# CLK_MUX.net
KiCad netlist of a schematic drawn in Altium Designer
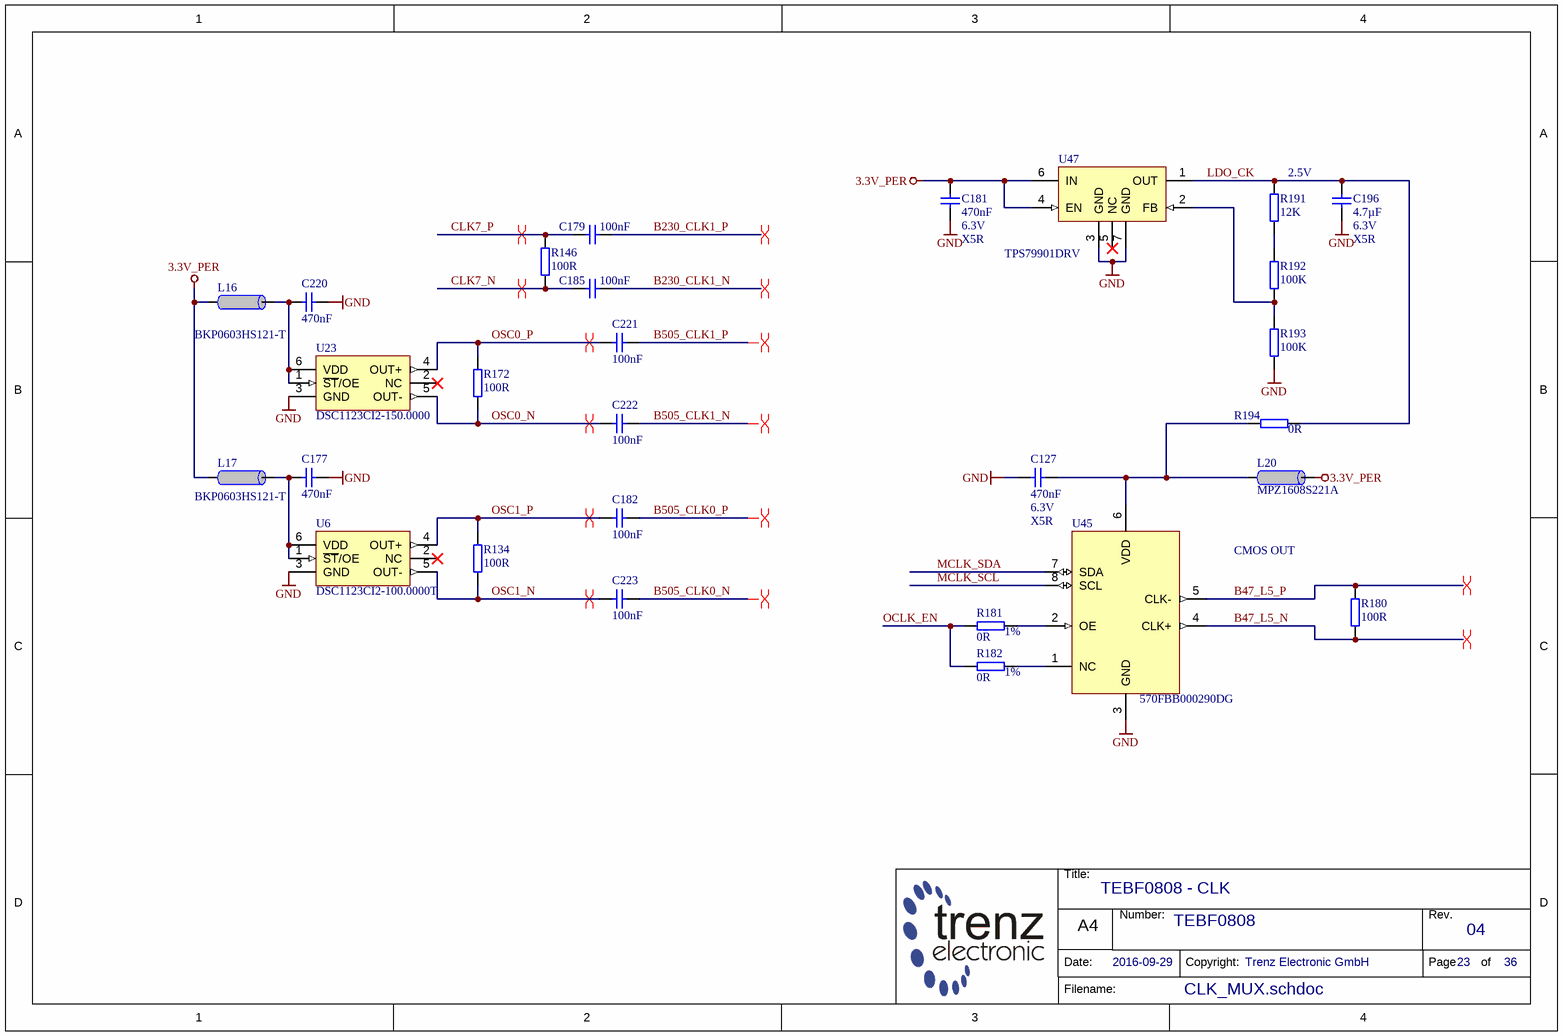
[diagram p0: CLK_MUX.schdoc]

(export (version "E")
  (design (tool "Eeschema 10.0.6"))
  (components
    (comp (ref "C127")
      (value "470nF")
      (footprint "CAPC1005X55N")
      (description "KON 470nF 6,3V X5R SMD")
      (fields (field (name "VOLTAGE") "6.3V") (field (name "TECHNOLOGY") "X5R"))
      (libsource (lib "TE") (part "CAP-NP"))
    )
    (comp (ref "C177")
      (value "470nF")
      (footprint "CAPC0603X33N")
      (description "KON 470nF X5R 6.3V SMD 20%")
      (fields (field (name "VOLTAGE") "6.3V") (field (name "TOLERANCE") "20%"))
      (libsource (lib "TE") (part "CAP-NP"))
    )
    (comp (ref "C179")
      (value "100nF")
      (footprint "CAPC0603X33N")
      (description "KON 100nF 6.3V X5R SMD 10%")
      (fields (field (name "VOLTAGE") "6.3V") (field (name "TOLERANCE") "10%"))
      (libsource (lib "TE") (part "CAP-NP"))
    )
    (comp (ref "C181")
      (value "470nF")
      (footprint "CAPC1005X55N")
      (description "KON 470nF 6,3V X5R SMD")
      (fields (field (name "VOLTAGE") "6.3V") (field (name "TECHNOLOGY") "X5R"))
      (libsource (lib "TE") (part "CAP-NP"))
    )
    (comp (ref "C182")
      (value "100nF")
      (footprint "CAPC0603X33N")
      (description "KON 100nF 6.3V X5R SMD 10%")
      (fields (field (name "VOLTAGE") "6.3V") (field (name "TOLERANCE") "10%"))
      (libsource (lib "TE") (part "CAP-NP"))
    )
    (comp (ref "C185")
      (value "100nF")
      (footprint "CAPC0603X33N")
      (description "KON 100nF 6.3V X5R SMD 10%")
      (fields (field (name "VOLTAGE") "6.3V") (field (name "TOLERANCE") "10%"))
      (libsource (lib "TE") (part "CAP-NP"))
    )
    (comp (ref "C196")
      (value "4.7µF")
      (footprint "CAPC1005X60N")
      (description "KON 4.7µF 6.3V X5R SMD 20%")
      (fields
        (field (name "VOLTAGE") "6.3V")
        (field (name "TECHNOLOGY") "X5R")
        (field (name "TOLERANCE") "20%")
      )
      (libsource (lib "TE") (part "CAP-NP"))
    )
    (comp (ref "C220")
      (value "470nF")
      (footprint "CAPC0603X33N")
      (description "KON 470nF X5R 6.3V SMD 20%")
      (fields (field (name "VOLTAGE") "6.3V") (field (name "TOLERANCE") "20%"))
      (libsource (lib "TE") (part "CAP-NP"))
    )
    (comp (ref "C221")
      (value "100nF")
      (footprint "CAPC0603X33N")
      (description "KON 100nF 6.3V X5R SMD 10%")
      (fields (field (name "VOLTAGE") "6.3V") (field (name "TOLERANCE") "10%"))
      (libsource (lib "TE") (part "CAP-NP"))
    )
    (comp (ref "C222")
      (value "100nF")
      (footprint "CAPC0603X33N")
      (description "KON 100nF 6.3V X5R SMD 10%")
      (fields (field (name "VOLTAGE") "6.3V") (field (name "TOLERANCE") "10%"))
      (libsource (lib "TE") (part "CAP-NP"))
    )
    (comp (ref "C223")
      (value "100nF")
      (footprint "CAPC0603X33N")
      (description "KON 100nF 6.3V X5R SMD 10%")
      (fields (field (name "VOLTAGE") "6.3V") (field (name "TOLERANCE") "10%"))
      (libsource (lib "TE") (part "CAP-NP"))
    )
    (comp (ref "L16")
      (value "BKP0603HS121-T")
      (footprint "INDC0603X33N")
      (description "Ferritdurchführung SMD 0201")
      (fields (field (name "TOLERANCE") "25%"))
      (libsource (lib "TE") (part "Ferritperle"))
    )
    (comp (ref "L17")
      (value "BKP0603HS121-T")
      (footprint "INDC0603X33N")
      (description "Ferritdurchführung SMD 0201")
      (fields (field (name "TOLERANCE") "25%"))
      (libsource (lib "TE") (part "Ferritperle"))
    )
    (comp (ref "L20")
      (value "MPZ1608S221A")
      (footprint "INDC1608X95N")
      (description "Ferritdurchführung MPZ1608S221A")
      (libsource (lib "") (part "Ferritperle_1"))
    )
    (comp (ref "R134")
      (value "100R")
      (footprint "RESC0603X26N")
      (description "WID SMD 100R 1% 0,05W")
      (fields (field (name "TOLERANCE") "1%"))
      (libsource (lib "TE") (part "RES"))
    )
    (comp (ref "R146")
      (value "100R")
      (footprint "RESC1005X40N")
      (description "WID SMD 100R 1% 0,063W")
      (fields (field (name "TOLERANCE") "1%"))
      (libsource (lib "TE") (part "RES"))
    )
    (comp (ref "R172")
      (value "100R")
      (footprint "RESC0603X26N")
      (description "WID SMD 100R 1% 0,05W")
      (fields (field (name "TOLERANCE") "1%"))
      (libsource (lib "TE") (part "RES"))
    )
    (comp (ref "R180")
      (value "100R")
      (footprint "RESC1005X40N")
      (description "WID SMD 100R 1% 0,063W")
      (fields (field (name "TOLERANCE") "1%"))
      (libsource (lib "TE") (part "RES"))
    )
    (comp (ref "R181")
      (value "0R")
      (footprint "RESC1005X40N")
      (description "WID SMD 0R")
      (fields (field (name "TOLERANCE") "1%"))
      (libsource (lib "TE") (part "RES"))
    )
    (comp (ref "R182")
      (value "0R")
      (footprint "RESC1005X40N")
      (description "WID SMD 0R")
      (fields (field (name "TOLERANCE") "1%"))
      (libsource (lib "TE") (part "RES"))
    )
    (comp (ref "R191")
      (value "12K")
      (footprint "RESC1005X40N")
      (description "WID SMD 12K 1% 0,063W")
      (fields (field (name "TOLERANCE") "1%"))
      (libsource (lib "TE") (part "RES"))
    )
    (comp (ref "R192")
      (value "100K")
      (footprint "RESC1005X40N")
      (description "WID SMD 100K 1% 0,063W")
      (fields (field (name "TOLERANCE") "1%"))
      (libsource (lib "TE") (part "RES"))
    )
    (comp (ref "R193")
      (value "100K")
      (footprint "RESC1005X40N")
      (description "WID SMD 100K 1% 0,063W")
      (fields (field (name "TOLERANCE") "1%"))
      (libsource (lib "TE") (part "RES"))
    )
    (comp (ref "R194")
      (value "0R")
      (footprint "RESC1005X40N")
      (description "WID SMD 0R")
      (fields (field (name "TOLERANCE") "1%"))
      (libsource (lib "TE") (part "RES"))
    )
    (comp (ref "U6")
      (value "DSC1123CI2-100.0000T")
      (footprint "PSON105P320X250X90-6N")
      (description "DSC1123CI2-100.0000T 100MHz LVDS clock")
      (fields (field (name "TOLERANCE") "25ppm"))
      (libsource (lib "TE") (part "SiT9102"))
    )
    (comp (ref "U23")
      (value "DSC1123CI2-150.0000")
      (footprint "PSON105P320X250X90-6N")
      (description "DSC1123CI2-150.0000 150MHz LVDS clock")
      (fields (field (name "TOLERANCE") "25ppm"))
      (libsource (lib "TE") (part "SiT9102"))
    )
    (comp (ref "U45")
      (value "570FBB000290DG")
      (footprint "OSCCC500X700X180-8N")
      (description "Si570 , LVDS , 2.5V , 250MHz")
      (libsource (lib "TE") (part "Si570"))
    )
    (comp (ref "U47")
      (value "TPS79901DRV")
      (footprint "SON65P200X210X80-7N-TI")
      (libsource (lib "TE") (part "TPS79901DRV"))
    )
  )
  (nets
    (net (code "1") (name "/B47_L5_N") (class "Default")
      (node (ref "R180") (pin "2") (pinfunction "2_2") (pintype "passive"))
      (node (ref "U45") (pin "4") (pinfunction "CLK+_4") (pintype "output"))
    )
    (net (code "2") (name "/B47_L5_P") (class "Default")
      (node (ref "R180") (pin "1") (pinfunction "1_1") (pintype "passive"))
      (node (ref "U45") (pin "5") (pinfunction "CLK-_5") (pintype "output"))
    )
    (net (code "3") (name "/B230_CLK1_N") (class "Default")
      (node (ref "C185") (pin "2") (pinfunction "2_2") (pintype "passive"))
    )
    (net (code "4") (name "/B230_CLK1_P") (class "Default")
      (node (ref "C179") (pin "2") (pinfunction "2_2") (pintype "passive"))
    )
    (net (code "5") (name "/B505_CLK0_N") (class "Default")
      (node (ref "C223") (pin "2") (pinfunction "2_2") (pintype "passive"))
    )
    (net (code "6") (name "/B505_CLK0_P") (class "Default")
      (node (ref "C182") (pin "2") (pinfunction "2_2") (pintype "passive"))
    )
    (net (code "7") (name "/B505_CLK1_N") (class "Default")
      (node (ref "C222") (pin "2") (pinfunction "2_2") (pintype "passive"))
    )
    (net (code "8") (name "/B505_CLK1_P") (class "Default")
      (node (ref "C221") (pin "2") (pinfunction "2_2") (pintype "passive"))
    )
    (net (code "9") (name "/CLK7_N") (class "Default")
      (node (ref "C185") (pin "1") (pinfunction "1_1") (pintype "passive"))
      (node (ref "R146") (pin "2") (pinfunction "2_2") (pintype "passive"))
    )
    (net (code "10") (name "/CLK7_P") (class "Default")
      (node (ref "C179") (pin "1") (pinfunction "1_1") (pintype "passive"))
      (node (ref "R146") (pin "1") (pinfunction "1_1") (pintype "passive"))
    )
    (net (code "11") (name "/LDO_CK") (class "Default")
      (node (ref "C196") (pin "1") (pinfunction "1_1") (pintype "passive"))
      (node (ref "R191") (pin "1") (pinfunction "1_1") (pintype "passive"))
      (node (ref "R194") (pin "1") (pinfunction "1_1") (pintype "passive"))
      (node (ref "U47") (pin "1") (pinfunction "OUT_1") (pintype "power_in"))
    )
    (net (code "12") (name "/MCLK_SCL") (class "Default")
      (node (ref "U45") (pin "8") (pinfunction "SCL_8") (pintype "bidirectional"))
    )
    (net (code "13") (name "/MCLK_SDA") (class "Default")
      (node (ref "U45") (pin "7") (pinfunction "SDA_7") (pintype "bidirectional"))
    )
    (net (code "14") (name "/OCLK_EN") (class "Default")
      (node (ref "R181") (pin "1") (pinfunction "1_1") (pintype "passive"))
      (node (ref "R182") (pin "1") (pinfunction "1_1") (pintype "passive"))
    )
    (net (code "15") (name "/OSC0_N") (class "Default")
      (node (ref "C222") (pin "1") (pinfunction "1_1") (pintype "passive"))
      (node (ref "R172") (pin "1") (pinfunction "1_1") (pintype "passive"))
      (node (ref "U23") (pin "5") (pinfunction "OUT-_5") (pintype "output"))
    )
    (net (code "16") (name "/OSC0_P") (class "Default")
      (node (ref "C221") (pin "1") (pinfunction "1_1") (pintype "passive"))
      (node (ref "R172") (pin "2") (pinfunction "2_2") (pintype "passive"))
      (node (ref "U23") (pin "4") (pinfunction "OUT+_4") (pintype "output"))
    )
    (net (code "17") (name "/OSC1_N") (class "Default")
      (node (ref "C223") (pin "1") (pinfunction "1_1") (pintype "passive"))
      (node (ref "R134") (pin "1") (pinfunction "1_1") (pintype "passive"))
      (node (ref "U6") (pin "5") (pinfunction "OUT-_5") (pintype "output"))
    )
    (net (code "18") (name "/OSC1_P") (class "Default")
      (node (ref "C182") (pin "1") (pinfunction "1_1") (pintype "passive"))
      (node (ref "R134") (pin "2") (pinfunction "2_2") (pintype "passive"))
      (node (ref "U6") (pin "4") (pinfunction "OUT+_4") (pintype "output"))
    )
    (net (code "19") (name "3.3V_PER") (class "Default")
      (node (ref "C181") (pin "2") (pinfunction "2_2") (pintype "passive"))
      (node (ref "L16") (pin "1") (pinfunction "1_1") (pintype "passive"))
      (node (ref "L17") (pin "1") (pinfunction "1_1") (pintype "passive"))
      (node (ref "L20") (pin "2") (pinfunction "2_2") (pintype "passive"))
      (node (ref "U47") (pin "4") (pinfunction "EN_4") (pintype "input"))
      (node (ref "U47") (pin "6") (pinfunction "IN_6") (pintype "power_in"))
    )
    (net (code "20") (name "GND") (class "Default")
      (node (ref "C127") (pin "1") (pinfunction "1_1") (pintype "passive"))
      (node (ref "C177") (pin "1") (pinfunction "1_1") (pintype "passive"))
      (node (ref "C181") (pin "1") (pinfunction "1_1") (pintype "passive"))
      (node (ref "C196") (pin "2") (pinfunction "2_2") (pintype "passive"))
      (node (ref "C220") (pin "1") (pinfunction "1_1") (pintype "passive"))
      (node (ref "R193") (pin "1") (pinfunction "1_1") (pintype "passive"))
      (node (ref "U23") (pin "3") (pinfunction "GND_3") (pintype "power_in"))
      (node (ref "U45") (pin "3") (pinfunction "GND_3") (pintype "power_in"))
      (node (ref "U47") (pin "3") (pinfunction "GND_3") (pintype "power_in"))
      (node (ref "U47") (pin "7") (pinfunction "GND_7") (pintype "power_in"))
      (node (ref "U6") (pin "3") (pinfunction "GND_3") (pintype "power_in"))
    )
    (net (code "21") (name "Net-(R191-Pad2)") (class "Default")
      (node (ref "R191") (pin "2") (pinfunction "2_2") (pintype "passive"))
      (node (ref "R192") (pin "2") (pinfunction "2_2") (pintype "passive"))
    )
    (net (code "22") (name "Net-(U6-VDD)") (class "Default")
      (node (ref "C177") (pin "2") (pinfunction "2_2") (pintype "passive"))
      (node (ref "L17") (pin "2") (pinfunction "2_2") (pintype "passive"))
      (node (ref "U6") (pin "1") (pinfunction "~{ST}/OE_1") (pintype "input"))
      (node (ref "U6") (pin "6") (pinfunction "VDD_6") (pintype "power_in"))
    )
    (net (code "23") (name "Net-(U23-VDD)") (class "Default")
      (node (ref "C220") (pin "2") (pinfunction "2_2") (pintype "passive"))
      (node (ref "L16") (pin "2") (pinfunction "2_2") (pintype "passive"))
      (node (ref "U23") (pin "1") (pinfunction "~{ST}/OE_1") (pintype "input"))
      (node (ref "U23") (pin "6") (pinfunction "VDD_6") (pintype "power_in"))
    )
    (net (code "24") (name "Net-(U45-NC)") (class "Default")
      (node (ref "R182") (pin "2") (pinfunction "2_2") (pintype "passive"))
      (node (ref "U45") (pin "1") (pinfunction "NC_1") (pintype "passive"))
    )
    (net (code "25") (name "Net-(U45-OE)") (class "Default")
      (node (ref "R181") (pin "2") (pinfunction "2_2") (pintype "passive"))
      (node (ref "U45") (pin "2") (pinfunction "OE_2") (pintype "input"))
    )
    (net (code "26") (name "Net-(U45-VDD)") (class "Default")
      (node (ref "C127") (pin "2") (pinfunction "2_2") (pintype "passive"))
      (node (ref "L20") (pin "1") (pinfunction "1_1") (pintype "passive"))
      (node (ref "R194") (pin "2") (pinfunction "2_2") (pintype "passive"))
      (node (ref "U45") (pin "6") (pinfunction "VDD_6") (pintype "power_in"))
    )
    (net (code "27") (name "Net-(U47-FB)") (class "Default")
      (node (ref "R192") (pin "1") (pinfunction "1_1") (pintype "passive"))
      (node (ref "R193") (pin "2") (pinfunction "2_2") (pintype "passive"))
      (node (ref "U47") (pin "2") (pinfunction "FB_2") (pintype "input"))
    )
    (net (code "28") (name "unconnected-(U6-NC-Pad2)") (class "Default")
      (node (ref "U6") (pin "2") (pinfunction "NC_2") (pintype "passive+no_connect"))
    )
    (net (code "29") (name "unconnected-(U23-NC-Pad2)") (class "Default")
      (node (ref "U23") (pin "2") (pinfunction "NC_2") (pintype "passive+no_connect"))
    )
    (net (code "30") (name "unconnected-(U47-NC-Pad5)") (class "Default")
      (node (ref "U47") (pin "5") (pinfunction "NC_5") (pintype "passive+no_connect"))
    )
  )
)
